# OutputConnectors.net
KiCad netlist of a schematic drawn in Altium Designer
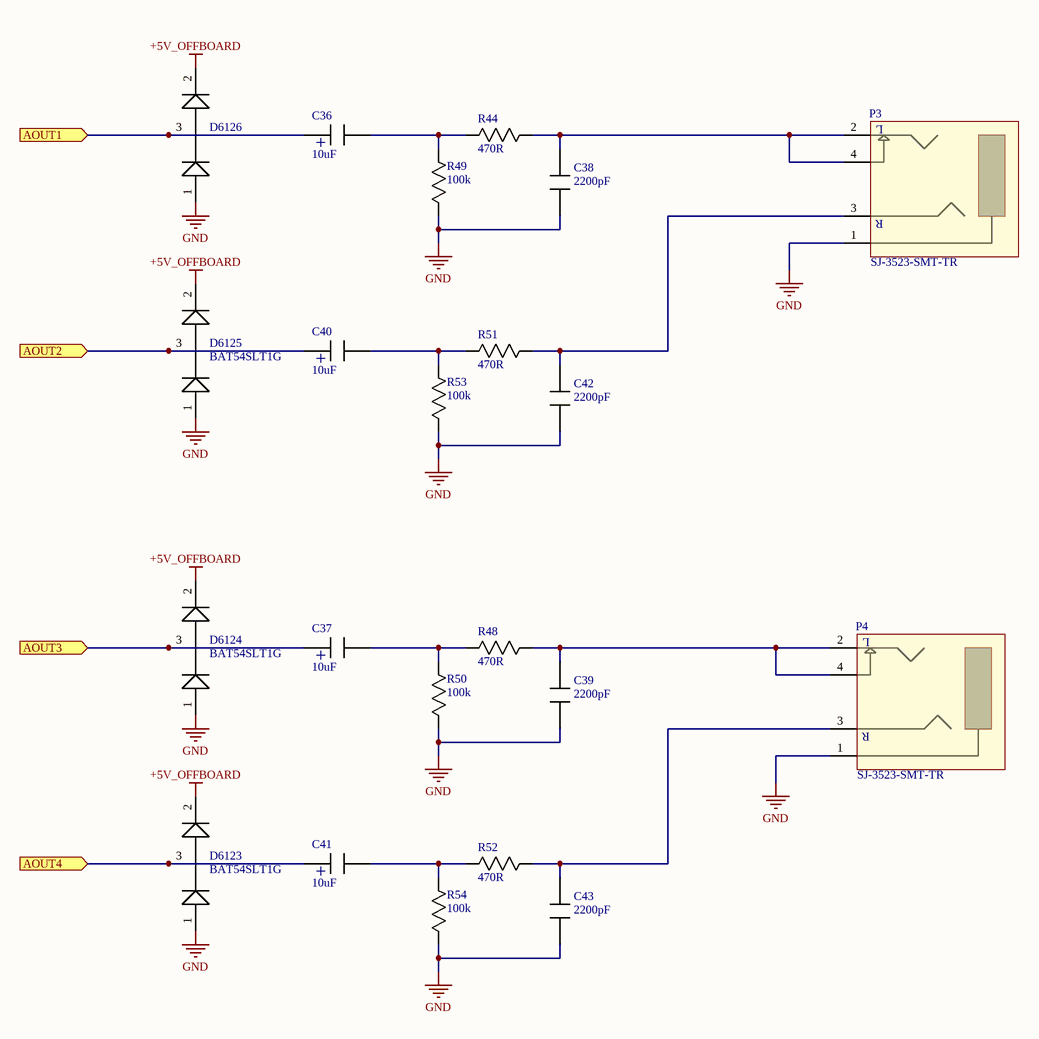
[diagram p0: OutputConnectors.SchDoc]

(export (version "E")
  (design (tool "Eeschema 10.0.6"))
  (components
    (comp (ref "C36")
      (value "10uF")
      (footprint "CAP_RAD_SMD_DIA157")
      (description "Capacitor")
      (fields (field (name "MFG") "Nichicon") (field (name "Comment") "Capacitor_Polarized"))
      (libsource (lib "INTER_2014") (part "Capacitor_Polarized"))
    )
    (comp (ref "C37")
      (value "10uF")
      (footprint "CAP_RAD_SMD_DIA157")
      (description "Capacitor")
      (fields (field (name "MFG") "Nichicon") (field (name "Comment") "Capacitor_Polarized"))
      (libsource (lib "INTER_2014") (part "Capacitor_Polarized"))
    )
    (comp (ref "C38")
      (value "2200pF")
      (footprint "0603")
      (description "Capacitor")
      (fields (field (name "MFG") "Murata"))
      (libsource (lib "INTER_2014") (part "Capacitor"))
    )
    (comp (ref "C39")
      (value "2200pF")
      (footprint "0603")
      (description "Capacitor")
      (fields (field (name "MFG") "Murata"))
      (libsource (lib "INTER_2014") (part "Capacitor"))
    )
    (comp (ref "C40")
      (value "10uF")
      (footprint "CAP_RAD_SMD_DIA157")
      (description "Capacitor")
      (fields (field (name "MFG") "Nichicon") (field (name "Comment") "Capacitor_Polarized"))
      (libsource (lib "INTER_2014") (part "Capacitor_Polarized"))
    )
    (comp (ref "C41")
      (value "10uF")
      (footprint "CAP_RAD_SMD_DIA157")
      (description "Capacitor")
      (fields (field (name "MFG") "Nichicon") (field (name "Comment") "Capacitor_Polarized"))
      (libsource (lib "INTER_2014") (part "Capacitor_Polarized"))
    )
    (comp (ref "C42")
      (value "2200pF")
      (footprint "0603")
      (description "Capacitor")
      (fields (field (name "MFG") "Murata"))
      (libsource (lib "INTER_2014") (part "Capacitor"))
    )
    (comp (ref "C43")
      (value "2200pF")
      (footprint "0603")
      (description "Capacitor")
      (fields (field (name "MFG") "Murata"))
      (libsource (lib "INTER_2014") (part "Capacitor"))
    )
    (comp (ref "D6123")
      (value "Diode_dual")
      (footprint "SOT23_132")
      (description "Diode")
      (fields (field (name "MFG") "Onsemi") (field (name "MFG_PN") "BAT54SLT1G"))
      (libsource (lib "INTER_2014") (part "Diode_dual"))
    )
    (comp (ref "D6124")
      (value "Diode_dual")
      (footprint "SOT23_132")
      (description "Diode")
      (fields (field (name "MFG") "Onsemi") (field (name "MFG_PN") "BAT54SLT1G"))
      (libsource (lib "INTER_2014") (part "Diode_dual"))
    )
    (comp (ref "D6125")
      (value "Diode_dual")
      (footprint "SOT23_132")
      (description "Diode")
      (fields (field (name "MFG") "Onsemi") (field (name "MFG_PN") "BAT54SLT1G"))
      (libsource (lib "INTER_2014") (part "Diode_dual"))
    )
    (comp (ref "D6126")
      (value "Diode_dual")
      (footprint "SOT23_132")
      (description "Diode")
      (fields (field (name "MFG") "Onsemi"))
      (libsource (lib "INTER_2014") (part "Diode_dual"))
    )
    (comp (ref "P3")
      (value "CON_AUDIO_3.5mm_TRS_ALT1")
      (footprint "CONN_3.5mm_CUI 3523-SMT")
      (description "Audio 3.5mm CUI SJ-3523-SMT-TR")
      (fields (field (name "MFG") "CUI") (field (name "MFG_PN") "SJ-3523-SMT-TR"))
      (libsource (lib "INTER_2014") (part "CON_AUDIO_3.5mm_TRS_ALT1"))
    )
    (comp (ref "P4")
      (value "CON_AUDIO_3.5mm_TRS_ALT1")
      (footprint "CONN_3.5mm_CUI 3523-SMT")
      (description "Audio 3.5mm CUI SJ-3523-SMT-TR")
      (fields (field (name "MFG") "CUI") (field (name "MFG_PN") "SJ-3523-SMT-TR"))
      (libsource (lib "INTER_2014") (part "CON_AUDIO_3.5mm_TRS_ALT1"))
    )
    (comp (ref "R44")
      (value "470R")
      (footprint "0603")
      (description "Resistor")
      (fields (field (name "MFG") "Yageo"))
      (libsource (lib "INTER_2014") (part "Resistor"))
    )
    (comp (ref "R48")
      (value "470R")
      (footprint "0603")
      (description "Resistor")
      (fields (field (name "MFG") "Yageo"))
      (libsource (lib "INTER_2014") (part "Resistor"))
    )
    (comp (ref "R49")
      (value "100k")
      (footprint "0603")
      (description "Resistor")
      (fields (field (name "MFG") "Yageo"))
      (libsource (lib "INTER_2014") (part "Resistor"))
    )
    (comp (ref "R50")
      (value "100k")
      (footprint "0603")
      (description "Resistor")
      (fields (field (name "MFG") "Yageo"))
      (libsource (lib "INTER_2014") (part "Resistor"))
    )
    (comp (ref "R51")
      (value "470R")
      (footprint "0603")
      (description "Resistor")
      (fields (field (name "MFG") "Yageo"))
      (libsource (lib "INTER_2014") (part "Resistor"))
    )
    (comp (ref "R52")
      (value "470R")
      (footprint "0603")
      (description "Resistor")
      (fields (field (name "MFG") "Yageo"))
      (libsource (lib "INTER_2014") (part "Resistor"))
    )
    (comp (ref "R53")
      (value "100k")
      (footprint "0603")
      (description "Resistor")
      (fields (field (name "MFG") "Yageo"))
      (libsource (lib "INTER_2014") (part "Resistor"))
    )
    (comp (ref "R54")
      (value "100k")
      (footprint "0603")
      (description "Resistor")
      (fields (field (name "MFG") "Yageo"))
      (libsource (lib "INTER_2014") (part "Resistor"))
    )
  )
  (nets
    (net (code "1") (name "+5V_OFFBOARD") (class "Default")
      (node (ref "D6123") (pin "2") (pinfunction "K_2") (pintype "passive"))
      (node (ref "D6124") (pin "2") (pinfunction "K_2") (pintype "passive"))
      (node (ref "D6125") (pin "2") (pinfunction "K_2") (pintype "passive"))
      (node (ref "D6126") (pin "2") (pinfunction "K_2") (pintype "passive"))
    )
    (net (code "2") (name "/AOUT1") (class "Default")
      (node (ref "C36") (pin "+") (pintype "passive"))
      (node (ref "D6126") (pin "3") (pinfunction "AK_3") (pintype "passive"))
    )
    (net (code "3") (name "/AOUT2") (class "Default")
      (node (ref "C40") (pin "+") (pintype "passive"))
      (node (ref "D6125") (pin "3") (pinfunction "AK_3") (pintype "passive"))
    )
    (net (code "4") (name "/AOUT3") (class "Default")
      (node (ref "C37") (pin "+") (pintype "passive"))
      (node (ref "D6124") (pin "3") (pinfunction "AK_3") (pintype "passive"))
    )
    (net (code "5") (name "/AOUT4") (class "Default")
      (node (ref "C41") (pin "+") (pintype "passive"))
      (node (ref "D6123") (pin "3") (pinfunction "AK_3") (pintype "passive"))
    )
    (net (code "6") (name "GND") (class "Default")
      (node (ref "C38") (pin "2") (pintype "passive"))
      (node (ref "C39") (pin "2") (pintype "passive"))
      (node (ref "C42") (pin "2") (pintype "passive"))
      (node (ref "C43") (pin "2") (pintype "passive"))
      (node (ref "D6123") (pin "1") (pinfunction "K_1") (pintype "passive"))
      (node (ref "D6124") (pin "1") (pinfunction "K_1") (pintype "passive"))
      (node (ref "D6125") (pin "1") (pinfunction "K_1") (pintype "passive"))
      (node (ref "D6126") (pin "1") (pinfunction "K_1") (pintype "passive"))
      (node (ref "P3") (pin "1") (pintype "passive"))
      (node (ref "P4") (pin "1") (pintype "passive"))
      (node (ref "R49") (pin "1") (pintype "passive"))
      (node (ref "R50") (pin "1") (pintype "passive"))
      (node (ref "R53") (pin "1") (pintype "passive"))
      (node (ref "R54") (pin "1") (pintype "passive"))
    )
    (net (code "7") (name "Net-(C36-Pad-)") (class "Default")
      (node (ref "C36") (pin "-") (pintype "passive"))
      (node (ref "R44") (pin "1") (pintype "passive"))
      (node (ref "R49") (pin "2") (pintype "passive"))
    )
    (net (code "8") (name "Net-(C37-Pad-)") (class "Default")
      (node (ref "C37") (pin "-") (pintype "passive"))
      (node (ref "R48") (pin "1") (pintype "passive"))
      (node (ref "R50") (pin "2") (pintype "passive"))
    )
    (net (code "9") (name "Net-(C40-Pad-)") (class "Default")
      (node (ref "C40") (pin "-") (pintype "passive"))
      (node (ref "R51") (pin "1") (pintype "passive"))
      (node (ref "R53") (pin "2") (pintype "passive"))
    )
    (net (code "10") (name "Net-(C41-Pad-)") (class "Default")
      (node (ref "C41") (pin "-") (pintype "passive"))
      (node (ref "R52") (pin "1") (pintype "passive"))
      (node (ref "R54") (pin "2") (pintype "passive"))
    )
    (net (code "11") (name "Net-(P3-L)") (class "Default")
      (node (ref "C38") (pin "1") (pintype "passive"))
      (node (ref "P3") (pin "2") (pinfunction "L_2") (pintype "passive"))
      (node (ref "P3") (pin "4") (pinfunction "NC_L_4") (pintype "passive"))
      (node (ref "R44") (pin "2") (pintype "passive"))
    )
    (net (code "12") (name "Net-(P3-R)") (class "Default")
      (node (ref "C42") (pin "1") (pintype "passive"))
      (node (ref "P3") (pin "3") (pinfunction "R_3") (pintype "passive"))
      (node (ref "R51") (pin "2") (pintype "passive"))
    )
    (net (code "13") (name "Net-(P4-L)") (class "Default")
      (node (ref "C39") (pin "1") (pintype "passive"))
      (node (ref "P4") (pin "2") (pinfunction "L_2") (pintype "passive"))
      (node (ref "P4") (pin "4") (pinfunction "NC_L_4") (pintype "passive"))
      (node (ref "R48") (pin "2") (pintype "passive"))
    )
    (net (code "14") (name "Net-(P4-R)") (class "Default")
      (node (ref "C43") (pin "1") (pintype "passive"))
      (node (ref "P4") (pin "3") (pinfunction "R_3") (pintype "passive"))
      (node (ref "R52") (pin "2") (pintype "passive"))
    )
  )
)
